# User_Terminal_Block.net
KiCad netlist of a schematic drawn in Altium Designer
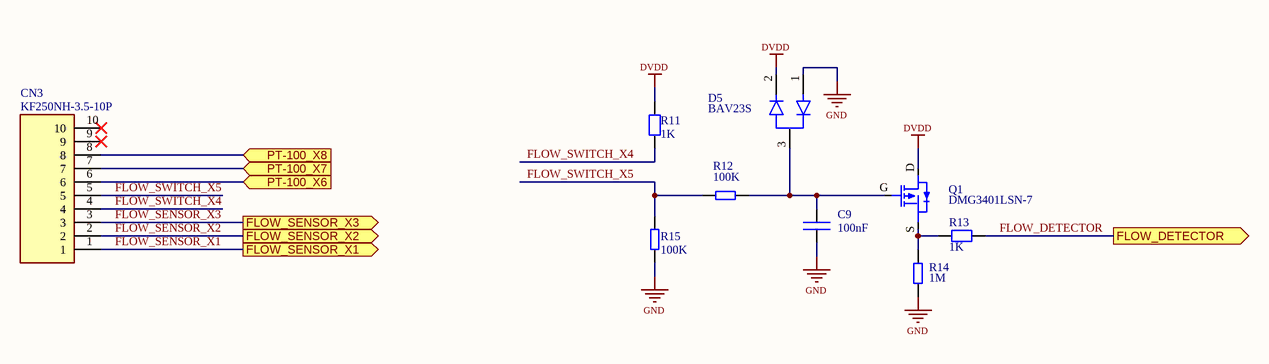
[diagram p0: User_Terminal_Block.SchDoc]

(export (version "E")
  (design (tool "Eeschema 10.0.6"))
  (components
    (comp (ref "C9")
      (value "100nF")
      (footprint "CAP_SM0603_YAGEOCC2_N")
      (description "CAP 100nF SM0603 X7R 50V YAGEO CC2")
      (fields
        (field (name "MANUFACTURER") "Yageo")
        (field (name "MANUFACTURER PART NUMBER") "CC0603KRX7R9BB104")
      )
      (libsource (lib "yageo") (part "CC0603KRX7R9BB104"))
    )
    (comp (ref "CN3")
      (value "KF250NH-3.5-10P")
      (footprint "KF250NH-3.5-10P")
      (description "PCB Terminal Block 1752188")
      (fields (field (name "MANUFACTURER") "cixi_kefa_elec") (field (name "VENDOR PART NUMBER") "C976564"))
      (libsource (lib "flowmeet") (part "KF250NH-3.5-10P"))
    )
    (comp (ref "D5")
      (value "BAV23S")
      (footprint "BAV23S")
      (description "DIODE ARRAY GP 250V 200MA SOT23")
      (fields (field (name "MANUFACTURER") "onsemi"))
      (libsource (lib "flowmeet") (part "BAV23S"))
    )
    (comp (ref "Q1")
      (value "DMG3401LSN-7")
      (footprint "DMG3401LSN-7")
      (description "P-CHANNEL ENHANCEMENT MODE MOSFET\r\nRDS(ON) = 85mΩ @ VGS = -2.5V -> ID -2.7A\r\nV(BR)DDS 30V")
      (fields (field (name "MANUFACTURER") "Diodes Incorporated"))
      (libsource (lib "flowmeet") (part "DMG3401LSN-7"))
    )
    (comp (ref "R11")
      (value "1K")
      (footprint "RES_SM0603_YAGEORC_N")
      (description "RES 1K SM0603 YAGEO RC_L")
      (fields
        (field (name "MANUFACTURER") "Yageo")
        (field (name "MANUFACTURER PART NUMBER") "RC0603FR-071KL")
      )
      (libsource (lib "yageo") (part "RC0603FR-071KL"))
    )
    (comp (ref "R12")
      (value "100K")
      (footprint "RES_SM0603_YAGEORC_N")
      (description "RES 100K SM0603 YAGEO RC_L")
      (fields
        (field (name "MANUFACTURER") "Yageo")
        (field (name "MANUFACTURER PART NUMBER") "RC0603FR-13100KL")
      )
      (libsource (lib "yageo") (part "RC0603FR-13100KL"))
    )
    (comp (ref "R13")
      (value "1K")
      (footprint "RES_SM0603_YAGEORC_N")
      (description "RES 1K SM0603 YAGEO RC_L")
      (fields
        (field (name "MANUFACTURER") "Yageo")
        (field (name "MANUFACTURER PART NUMBER") "RC0603FR-071KL")
      )
      (libsource (lib "") (part "RC0603FR-071KL_1"))
    )
    (comp (ref "R14")
      (value "1M")
      (footprint "RES_SM0603_YAGEORC_N")
      (description "RES 1M SM0603 YAGEO RC_L")
      (fields
        (field (name "MANUFACTURER") "Yageo")
        (field (name "MANUFACTURER PART NUMBER") "RC0603FR-071ML")
      )
      (libsource (lib "yageo") (part "RC0603FR-071ML"))
    )
    (comp (ref "R15")
      (value "100K")
      (footprint "RES_SM0603_YAGEORC_N")
      (description "RES 100K SM0603 YAGEO RC_L")
      (fields
        (field (name "MANUFACTURER") "Yageo")
        (field (name "MANUFACTURER PART NUMBER") "RC0603FR-13100KL")
      )
      (libsource (lib "") (part "RC0603FR-13100KL_1"))
    )
  )
  (nets
    (net (code "1") (name "/FLOW_DETECTOR") (class "Default")
      (node (ref "R13") (pin "2") (pintype "passive"))
    )
    (net (code "2") (name "/FLOW_SENSOR_X1") (class "Default")
      (node (ref "CN3") (pin "1") (pinfunction "1_1") (pintype "passive"))
    )
    (net (code "3") (name "/FLOW_SENSOR_X2") (class "Default")
      (node (ref "CN3") (pin "2") (pinfunction "2_2") (pintype "passive"))
    )
    (net (code "4") (name "/FLOW_SENSOR_X3") (class "Default")
      (node (ref "CN3") (pin "3") (pinfunction "3_3") (pintype "passive"))
    )
    (net (code "5") (name "/FLOW_SWITCH_X4") (class "Default")
      (node (ref "CN3") (pin "4") (pinfunction "4_4") (pintype "passive"))
      (node (ref "R11") (pin "1") (pintype "passive"))
    )
    (net (code "6") (name "/FLOW_SWITCH_X5") (class "Default")
      (node (ref "CN3") (pin "5") (pinfunction "5_5") (pintype "passive"))
      (node (ref "R12") (pin "1") (pintype "passive"))
      (node (ref "R15") (pin "2") (pintype "passive"))
    )
    (net (code "7") (name "/PT-100_X6") (class "Default")
      (node (ref "CN3") (pin "6") (pinfunction "6_6") (pintype "passive"))
    )
    (net (code "8") (name "/PT-100_X7") (class "Default")
      (node (ref "CN3") (pin "7") (pinfunction "7_7") (pintype "passive"))
    )
    (net (code "9") (name "/PT-100_X8") (class "Default")
      (node (ref "CN3") (pin "8") (pinfunction "8_8") (pintype "passive"))
    )
    (net (code "10") (name "DVDD") (class "Default")
      (node (ref "D5") (pin "2") (pinfunction "2_2") (pintype "passive"))
      (node (ref "Q1") (pin "D") (pinfunction "D_D") (pintype "passive"))
      (node (ref "R11") (pin "2") (pintype "passive"))
    )
    (net (code "11") (name "GND") (class "Default")
      (node (ref "C9") (pin "2") (pintype "passive"))
      (node (ref "D5") (pin "1") (pinfunction "1_1") (pintype "passive"))
      (node (ref "R14") (pin "1") (pintype "passive"))
      (node (ref "R15") (pin "1") (pintype "passive"))
    )
    (net (code "12") (name "Net-(C9-Pad1)") (class "Default")
      (node (ref "C9") (pin "1") (pintype "passive"))
      (node (ref "D5") (pin "3") (pinfunction "3_3") (pintype "passive"))
      (node (ref "Q1") (pin "G") (pinfunction "G_G") (pintype "passive"))
      (node (ref "R12") (pin "2") (pintype "passive"))
    )
    (net (code "13") (name "Net-(Q1-PadS)") (class "Default")
      (node (ref "Q1") (pin "S") (pinfunction "S_S") (pintype "passive"))
      (node (ref "R13") (pin "1") (pintype "passive"))
      (node (ref "R14") (pin "2") (pintype "passive"))
    )
    (net (code "14") (name "unconnected-(CN3-Pad9)") (class "Default")
      (node (ref "CN3") (pin "9") (pinfunction "9_9") (pintype "passive+no_connect"))
    )
    (net (code "15") (name "unconnected-(CN3-Pad10)") (class "Default")
      (node (ref "CN3") (pin "10") (pinfunction "10_10") (pintype "passive+no_connect"))
    )
  )
)
